# 5_4_transceiver.net
KiCad netlist of a schematic drawn in Altium Designer
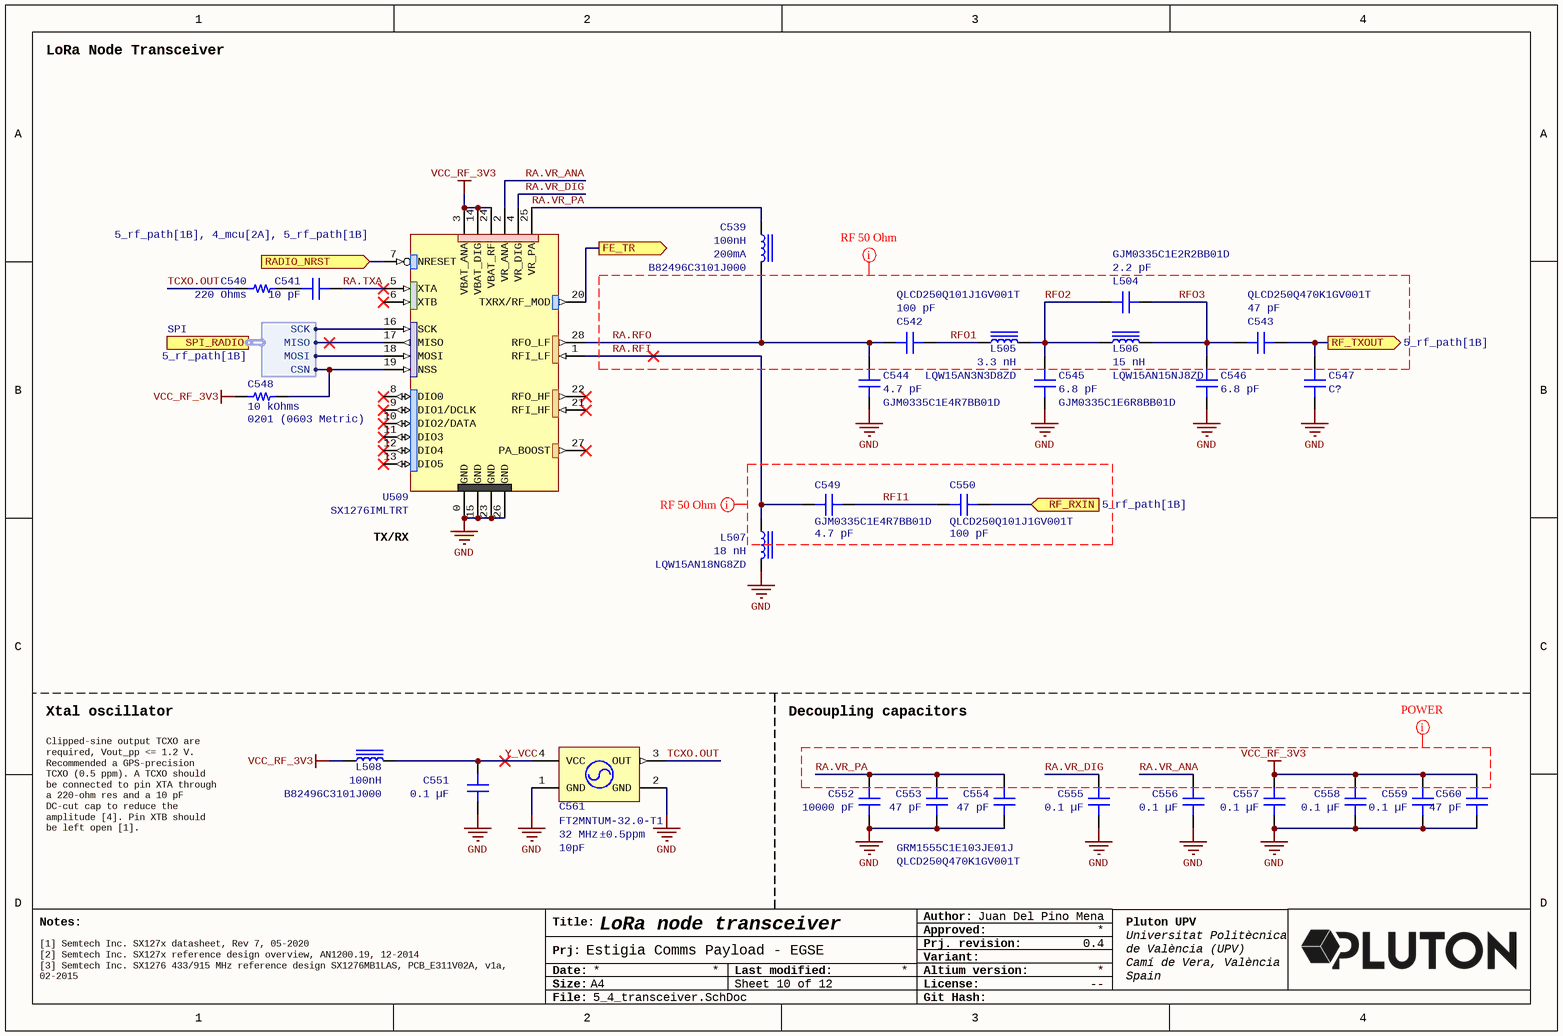
[diagram p0: 5_4_transceiver.SchDoc]

(export (version "E")
  (design (tool "Eeschema 10.0.6"))
  (components
    (comp (ref "C539")
      (value "100nH")
      (footprint "IND 0603_1608 RF WW")
      (description "FIXED IND 100NH 200MA 1.8 OHM")
      (fields
        (field (name "PART NUMBER") "B82496C3101J000")
        (field (name "CURRENT RATING (AMPS)") "200mA")
        (field (name "MANUFACTURER") "TDK Electronics Inc.")
        (field (name "TOLERANCE") "±5%")
      )
      (libsource (lib "Celestial Altium Library - altium_library") (part "Inductor"))
    )
    (comp (ref "C540")
      (value "220 Ohms")
      (footprint "RES 0201_0603")
      (description "RES 220 OHM 1% 1/20W 0201")
      (fields (field (name "PART NUMBER") "RC0201FR-07220RL") (field (name "MANUFACTURER") "Yageo"))
      (libsource (lib "Celestial Altium Library - altium_library") (part "Resistor"))
    )
    (comp (ref "C541")
      (value "10 pF")
      (footprint "CAP 0201_0603")
      (description "CAP CER 10PF 25V C0G/NP0 0201")
      (fields
        (field (name "PART NUMBER") "GJM0335C1E100GB01D")
        (field (name "MANUFACTURER") "Murata Electronics")
      )
      (libsource (lib "Celestial Altium Library - altium_library") (part "Capacitor"))
    )
    (comp (ref "C542")
      (value "100 pF")
      (footprint "CAP 0201_0603 RF")
      (description "CAP CER 100PF 25V C0G/NP0 0201")
      (fields
        (field (name "PART NUMBER") "QLCD250Q101J1GV001T")
        (field (name "CAPACITANCE") "100 pF")
        (field (name "MANUFACTURER") "Johanson Technology Inc.")
        (field (name "TOLERANCE") "±5%")
      )
      (libsource (lib "Celestial Altium Library - altium_library") (part "Capacitor"))
    )
    (comp (ref "C543")
      (value "47 pF")
      (footprint "CAP 0201_0603 RF")
      (description "CAP CER 47PF 25V NP0 0201")
      (fields
        (field (name "PART NUMBER") "QLCD250Q470K1GV001T")
        (field (name "CAPACITANCE") "47 pF")
        (field (name "MANUFACTURER") "Johanson Technology Inc.")
        (field (name "TOLERANCE") "±10%")
      )
      (libsource (lib "Celestial Altium Library - altium_library") (part "Capacitor"))
    )
    (comp (ref "C544")
      (value "4.7 pF")
      (footprint "CAP 0201_0603 RF")
      (description "CAP CER 4.7PF 25V C0G/NP0 0201")
      (fields
        (field (name "PART NUMBER") "GJM0335C1E4R7BB01D")
        (field (name "MANUFACTURER") "Murata Electronics")
        (field (name "TOLERANCE") "±0.1pF")
      )
      (libsource (lib "Celestial Altium Library - altium_library") (part "Capacitor"))
    )
    (comp (ref "C545")
      (value "6.8 pF")
      (footprint "CAP 0201_0603 RF")
      (description "CAP CER 6.8PF 25V C0G/NP0 0201")
      (fields
        (field (name "PART NUMBER") "GJM0335C1E6R8BB01D")
        (field (name "MANUFACTURER") "Murata Electronics")
        (field (name "TOLERANCE") "±0.1pF")
      )
      (libsource (lib "Celestial Altium Library - altium_library") (part "Capacitor"))
    )
    (comp (ref "C546")
      (value "6.8 pF")
      (footprint "CAP 0201_0603 RF")
      (description "CAP CER 6.8PF 25V C0G/NP0 0201")
      (fields
        (field (name "PART NUMBER") "GJM0335C1E6R8BB01D")
        (field (name "MANUFACTURER") "Murata Electronics")
      )
      (libsource (lib "Celestial Altium Library - altium_library") (part "Capacitor"))
    )
    (comp (ref "C547")
      (value "C?")
      (footprint "CAP 0201_0603")
      (description "CAP CER 2.2PF 25V C0G/NP0 0201")
      (fields
        (field (name "PART NUMBER") "GJM0335C1E2R2BB01D")
        (field (name "MANUFACTURER") "Murata Electronics")
      )
      (libsource (lib "Celestial Altium Library - altium_library") (part "Capacitor"))
    )
    (comp (ref "C548")
      (value "10 kOhms")
      (footprint "RES 0201_0603")
      (description "RES SMD 10K OHM 1% 1/20W 0201")
      (fields
        (field (name "PART NUMBER") "AF0201FR-0710KL")
        (field (name "MANUFACTURER") "Yageo")
        (field (name "PACKAGE / CASE") "0201 (0603 Metric)")
      )
      (libsource (lib "Celestial Altium Library - altium_library") (part "Resistor"))
    )
    (comp (ref "C549")
      (value "4.7 pF")
      (footprint "CAP 0201_0603 RF")
      (description "CAP CER 4.7PF 25V C0G/NP0 0201")
      (fields
        (field (name "PART NUMBER") "GJM0335C1E4R7BB01D")
        (field (name "MANUFACTURER") "Murata Electronics")
        (field (name "TOLERANCE") "±0.1pF")
      )
      (libsource (lib "Celestial Altium Library - altium_library") (part "Capacitor"))
    )
    (comp (ref "C550")
      (value "100 pF")
      (footprint "CAP 0201_0603 RF")
      (description "CAP CER 100PF 25V C0G/NP0 0201")
      (fields
        (field (name "PART NUMBER") "QLCD250Q101J1GV001T")
        (field (name "CAPACITANCE") "100 pF")
        (field (name "MANUFACTURER") "Johanson Technology Inc.")
        (field (name "TOLERANCE") "±5%")
      )
      (libsource (lib "Celestial Altium Library - altium_library") (part "Capacitor"))
    )
    (comp (ref "C551")
      (value "0.1 µF")
      (footprint "CAP 0402_1005")
      (description "CAP CER 0402 0.1UF 16V X7R 10%")
      (fields (field (name "PART NUMBER") "C0402C104K4RECAUTO") (field (name "MANUFACTURER") "KEMET"))
      (libsource (lib "Celestial Altium Library - altium_library") (part "Capacitor"))
    )
    (comp (ref "C552")
      (value "10000 pF")
      (footprint "CAP 0402_1005")
      (description "CAP CER 10000PF 25V C0G/NP0 0402")
      (fields
        (field (name "PART NUMBER") "GRM1555C1E103JE01J")
        (field (name "MANUFACTURER") "Murata Electronics")
        (field (name "TOLERANCE") "±5%")
      )
      (libsource (lib "Celestial Altium Library - altium_library") (part "Capacitor"))
    )
    (comp (ref "C553")
      (value "47 pF")
      (footprint "CAP 0201_0603 RF")
      (description "CAP CER 47PF 25V NP0 0201")
      (fields
        (field (name "PART NUMBER") "QLCD250Q470K1GV001T")
        (field (name "CAPACITANCE") "47 pF")
        (field (name "MANUFACTURER") "Johanson Technology Inc.")
      )
      (libsource (lib "Celestial Altium Library - altium_library") (part "Capacitor"))
    )
    (comp (ref "C554")
      (value "47 pF")
      (footprint "CAP 0201_0603 RF")
      (description "CAP CER 47PF 25V NP0 0201")
      (fields
        (field (name "PART NUMBER") "QLCD250Q470K1GV001T")
        (field (name "CAPACITANCE") "47 pF")
        (field (name "MANUFACTURER") "Johanson Technology Inc.")
        (field (name "TOLERANCE") "±10%")
      )
      (libsource (lib "Celestial Altium Library - altium_library") (part "Capacitor"))
    )
    (comp (ref "C555")
      (value "0.1 µF")
      (footprint "CAP 0402_1005")
      (description "CAP CER 0402 0.1UF 16V X7R 10%")
      (fields (field (name "PART NUMBER") "C0402C104K4RECAUTO") (field (name "MANUFACTURER") "KEMET"))
      (libsource (lib "Celestial Altium Library - altium_library") (part "Capacitor"))
    )
    (comp (ref "C556")
      (value "0.1 µF")
      (footprint "CAP 0402_1005")
      (description "CAP CER 0402 0.1UF 16V X7R 10%")
      (fields (field (name "PART NUMBER") "C0402C104K4RECAUTO") (field (name "MANUFACTURER") "KEMET"))
      (libsource (lib "Celestial Altium Library - altium_library") (part "Capacitor"))
    )
    (comp (ref "C557")
      (value "0.1 µF")
      (footprint "CAP 0402_1005")
      (description "CAP CER 0402 0.1UF 16V X7R 10%")
      (fields (field (name "PART NUMBER") "C0402C104K4RECAUTO") (field (name "MANUFACTURER") "KEMET"))
      (libsource (lib "Celestial Altium Library - altium_library") (part "Capacitor"))
    )
    (comp (ref "C558")
      (value "0.1 µF")
      (footprint "CAP 0402_1005")
      (description "CAP CER 0402 0.1UF 16V X7R 10%")
      (fields (field (name "PART NUMBER") "C0402C104K4RECAUTO") (field (name "MANUFACTURER") "KEMET"))
      (libsource (lib "Celestial Altium Library - altium_library") (part "Capacitor"))
    )
    (comp (ref "C559")
      (value "0.1 µF")
      (footprint "CAP 0402_1005")
      (description "CAP CER 0402 0.1UF 16V X7R 10%")
      (fields (field (name "PART NUMBER") "C0402C104K4RECAUTO") (field (name "MANUFACTURER") "KEMET"))
      (libsource (lib "Celestial Altium Library - altium_library") (part "Capacitor"))
    )
    (comp (ref "C560")
      (value "47 pF")
      (footprint "CAP 0201_0603 RF")
      (description "CAP CER 47PF 25V NP0 0201")
      (fields
        (field (name "PART NUMBER") "QLCD250Q470K1GV001T")
        (field (name "CAPACITANCE") "47 pF")
        (field (name "MANUFACTURER") "Johanson Technology Inc.")
      )
      (libsource (lib "Celestial Altium Library - altium_library") (part "Capacitor"))
    )
    (comp (ref "C561")
      (value "FT2MNTUM-32.0-T1")
      (footprint "TCXO-XTAL-FT2MN")
      (fields
        (field (name "PART NUMBER") "FT2MNTUM-32.0-T1")
        (field (name "FREQUENCY") "32 MHz")
        (field (name "TOLERANCE") "±0.5ppm")
        (field (name "LOAD CAPACITANCE") "10pF")
      )
      (libsource (lib "rf") (part "FT2MNTUM-32.0-T1"))
    )
    (comp (ref "L504")
      (value "2.2 pF")
      (footprint "CAP 0201_0603")
      (description "CAP CER 2.2PF 25V C0G/NP0 0201")
      (fields
        (field (name "PART NUMBER") "GJM0335C1E2R2BB01D")
        (field (name "MANUFACTURER") "Murata Electronics")
        (field (name "TOLERANCE") "±0.1pF")
      )
      (libsource (lib "Celestial Altium Library - altium_library") (part "Capacitor"))
    )
    (comp (ref "L505")
      (value "3.3 nH")
      (footprint "IND 0402_1005 RF WW")
      (description "FIXED IND 3.3NH 2A 0.03OHM SMD")
      (fields
        (field (name "PART NUMBER") "LQW15AN3N3D8ZD")
        (field (name "INDUCTANCE") "3.3 nH")
        (field (name "MANUFACTURER") "Murata Electronics")
        (field (name "TOLERANCE") "±0.5nH")
      )
      (libsource (lib "Celestial Altium Library - altium_library") (part "Inductor"))
    )
    (comp (ref "L506")
      (value "15 nH")
      (footprint "IND 0402_1005 RF WW")
      (description "FIXED IND 15NH 1.15A 0.114OHM SM")
      (fields
        (field (name "PART NUMBER") "LQW15AN15NJ8ZD")
        (field (name "INDUCTANCE") "15 nH")
        (field (name "MANUFACTURER") "Murata Electronics")
        (field (name "TOLERANCE") "±5%")
      )
      (libsource (lib "Celestial Altium Library - altium_library") (part "Inductor"))
    )
    (comp (ref "L507")
      (value "18 nH")
      (footprint "IND 0402_1005 RF WW")
      (description "FIXED IND 18NH 1.05A 0.13OHM SMD")
      (fields
        (field (name "PART NUMBER") "LQW15AN18NG8ZD")
        (field (name "INDUCTANCE") "18 nH")
        (field (name "MANUFACTURER") "Murata Electronics")
        (field (name "TOLERANCE") "±2%")
      )
      (libsource (lib "Celestial Altium Library - altium_library") (part "Inductor"))
    )
    (comp (ref "L508")
      (value "100nH")
      (footprint "IND 0603_1608 RF WW")
      (description "FIXED IND 100NH 200MA 1.8 OHM")
      (fields
        (field (name "PART NUMBER") "B82496C3101J000")
        (field (name "MANUFACTURER") "TDK Electronics Inc.")
        (field (name "TOLERANCE") "±5%")
      )
      (libsource (lib "Celestial Altium Library - altium_library") (part "Inductor"))
    )
    (comp (ref "U509")
      (value "SX1276IMLTRT")
      (footprint "ics:QFN-28")
      (description "137 MHz to 1020 MHz Low Power Long Range Transceiver")
      (libsource (lib "lora") (part "SX1276IMLTRT"))
    )
  )
  (nets
    (net (code "2") (name "/CSN") (class "Default")
      (node (ref "C548") (pin "2") (pinfunction "2_2") (pintype "passive"))
      (node (ref "U509") (pin "19") (pinfunction "NSS_19") (pintype "input"))
    )
    (net (code "3") (name "/FE_TR") (class "Default")
      (node (ref "U509") (pin "20") (pinfunction "TXRX/RF_MOD_20") (pintype "output"))
    )
    (net (code "4") (name "/MISO") (class "Default")
      (node (ref "U509") (pin "17") (pinfunction "MISO_17") (pintype "output"))
    )
    (net (code "5") (name "/MOSI") (class "Default")
      (node (ref "U509") (pin "18") (pinfunction "MOSI_18") (pintype "input"))
    )
    (net (code "7") (name "/RA.RFI") (class "Default")
      (node (ref "C549") (pin "2") (pinfunction "2_2") (pintype "passive"))
      (node (ref "L507") (pin "1") (pinfunction "1_1") (pintype "passive"))
      (node (ref "U509") (pin "1") (pinfunction "RFI_LF_1") (pintype "input"))
    )
    (net (code "8") (name "/RA.RFO") (class "Default")
      (node (ref "C539") (pin "2") (pinfunction "2_2") (pintype "passive"))
      (node (ref "C542") (pin "1") (pinfunction "1_1") (pintype "passive"))
      (node (ref "C544") (pin "2") (pinfunction "2_2") (pintype "passive"))
      (node (ref "U509") (pin "28") (pinfunction "RFO_LF_28") (pintype "output"))
    )
    (net (code "9") (name "/RA.TXA") (class "Default")
      (node (ref "C541") (pin "1") (pinfunction "1_1") (pintype "passive"))
      (node (ref "U509") (pin "5") (pinfunction "XTA_5") (pintype "input"))
    )
    (net (code "10") (name "/RA.VR_ANA") (class "Default")
      (node (ref "C556") (pin "2") (pinfunction "2_2") (pintype "passive"))
      (node (ref "U509") (pin "2") (pinfunction "VR_ANA_2") (pintype "power_in"))
    )
    (net (code "11") (name "/RA.VR_DIG") (class "Default")
      (node (ref "C555") (pin "2") (pinfunction "2_2") (pintype "passive"))
      (node (ref "U509") (pin "4") (pinfunction "VR_DIG_4") (pintype "power_in"))
    )
    (net (code "12") (name "/RA.VR_PA") (class "Default")
      (node (ref "C539") (pin "1") (pinfunction "1_1") (pintype "passive"))
      (node (ref "C552") (pin "2") (pinfunction "2_2") (pintype "passive"))
      (node (ref "C553") (pin "2") (pinfunction "2_2") (pintype "passive"))
      (node (ref "C554") (pin "1") (pinfunction "1_1") (pintype "passive"))
      (node (ref "U509") (pin "25") (pinfunction "VR_PA_25") (pintype "power_in"))
    )
    (net (code "13") (name "/RADIO_NRST") (class "Default")
      (node (ref "U509") (pin "7") (pinfunction "NRESET_7") (pintype "input"))
    )
    (net (code "14") (name "/RFI1") (class "Default")
      (node (ref "C549") (pin "1") (pinfunction "1_1") (pintype "passive"))
      (node (ref "C550") (pin "2") (pinfunction "2_2") (pintype "passive"))
    )
    (net (code "15") (name "/RFO1") (class "Default")
      (node (ref "C542") (pin "2") (pinfunction "2_2") (pintype "passive"))
      (node (ref "L505") (pin "1") (pinfunction "1_1") (pintype "passive"))
    )
    (net (code "16") (name "/RFO2") (class "Default")
      (node (ref "C545") (pin "2") (pinfunction "2_2") (pintype "passive"))
      (node (ref "L504") (pin "1") (pinfunction "1_1") (pintype "passive"))
      (node (ref "L505") (pin "2") (pinfunction "2_2") (pintype "passive"))
      (node (ref "L506") (pin "1") (pinfunction "1_1") (pintype "passive"))
    )
    (net (code "17") (name "/RFO3") (class "Default")
      (node (ref "C543") (pin "1") (pinfunction "1_1") (pintype "passive"))
      (node (ref "C546") (pin "2") (pinfunction "2_2") (pintype "passive"))
      (node (ref "L504") (pin "2") (pinfunction "2_2") (pintype "passive"))
      (node (ref "L506") (pin "2") (pinfunction "2_2") (pintype "passive"))
    )
    (net (code "18") (name "/RF_RXIN") (class "Default")
      (node (ref "C550") (pin "1") (pinfunction "1_1") (pintype "passive"))
    )
    (net (code "19") (name "/RF_TXOUT") (class "Default")
      (node (ref "C543") (pin "2") (pinfunction "2_2") (pintype "passive"))
      (node (ref "C547") (pin "2") (pinfunction "2_2") (pintype "passive"))
    )
    (net (code "20") (name "/SCK") (class "Default")
      (node (ref "U509") (pin "16") (pinfunction "SCK_16") (pintype "input"))
    )
    (net (code "23") (name "/TCXO.OUT") (class "Default")
      (node (ref "C540") (pin "1") (pinfunction "1_1") (pintype "passive"))
      (node (ref "C561") (pin "3") (pinfunction "OUT_3") (pintype "output"))
    )
    (net (code "24") (name "/Y_VCC") (class "Default")
      (node (ref "C551") (pin "2") (pinfunction "2_2") (pintype "passive"))
      (node (ref "C561") (pin "4") (pinfunction "VCC_4") (pintype "power_in"))
      (node (ref "L508") (pin "2") (pinfunction "2_2") (pintype "passive"))
    )
    (net (code "25") (name "GND") (class "Default")
      (node (ref "C544") (pin "1") (pinfunction "1_1") (pintype "passive"))
      (node (ref "C545") (pin "1") (pinfunction "1_1") (pintype "passive"))
      (node (ref "C546") (pin "1") (pinfunction "1_1") (pintype "passive"))
      (node (ref "C547") (pin "1") (pinfunction "1_1") (pintype "passive"))
      (node (ref "C551") (pin "1") (pinfunction "1_1") (pintype "passive"))
      (node (ref "C552") (pin "1") (pinfunction "1_1") (pintype "passive"))
      (node (ref "C553") (pin "1") (pinfunction "1_1") (pintype "passive"))
      (node (ref "C554") (pin "2") (pinfunction "2_2") (pintype "passive"))
      (node (ref "C555") (pin "1") (pinfunction "1_1") (pintype "passive"))
      (node (ref "C556") (pin "1") (pinfunction "1_1") (pintype "passive"))
      (node (ref "C557") (pin "1") (pinfunction "1_1") (pintype "passive"))
      (node (ref "C558") (pin "1") (pinfunction "1_1") (pintype "passive"))
      (node (ref "C559") (pin "1") (pinfunction "1_1") (pintype "passive"))
      (node (ref "C560") (pin "1") (pinfunction "1_1") (pintype "passive"))
      (node (ref "C561") (pin "1") (pinfunction "GND_1") (pintype "power_in"))
      (node (ref "C561") (pin "2") (pinfunction "GND_2") (pintype "power_in"))
      (node (ref "L507") (pin "2") (pinfunction "2_2") (pintype "passive"))
      (node (ref "U509") (pin "0") (pinfunction "GND_0") (pintype "power_in"))
      (node (ref "U509") (pin "15") (pinfunction "GND_15") (pintype "power_in"))
      (node (ref "U509") (pin "23") (pinfunction "GND_23") (pintype "power_in"))
      (node (ref "U509") (pin "26") (pinfunction "GND_26") (pintype "power_in"))
    )
    (net (code "26") (name "Net-(C540-Pad2)") (class "Default")
      (node (ref "C540") (pin "2") (pinfunction "2_2") (pintype "passive"))
      (node (ref "C541") (pin "2") (pinfunction "2_2") (pintype "passive"))
    )
    (net (code "27") (name "VCC_RF_3V3") (class "Default")
      (node (ref "C548") (pin "1") (pinfunction "1_1") (pintype "passive"))
      (node (ref "C557") (pin "2") (pinfunction "2_2") (pintype "passive"))
      (node (ref "C558") (pin "2") (pinfunction "2_2") (pintype "passive"))
      (node (ref "C559") (pin "2") (pinfunction "2_2") (pintype "passive"))
      (node (ref "C560") (pin "2") (pinfunction "2_2") (pintype "passive"))
      (node (ref "L508") (pin "1") (pinfunction "1_1") (pintype "passive"))
      (node (ref "U509") (pin "14") (pinfunction "VBAT_DIG_14") (pintype "power_in"))
      (node (ref "U509") (pin "24") (pinfunction "VBAT_RF_24") (pintype "power_in"))
      (node (ref "U509") (pin "3") (pinfunction "VBAT_ANA_3") (pintype "power_in"))
    )
    (net (code "28") (name "unconnected-(U509-DIO0-Pad8)") (class "Default")
      (node (ref "U509") (pin "8") (pinfunction "DIO0_8") (pintype "bidirectional+no_connect"))
    )
    (net (code "29") (name "unconnected-(U509-DIO1{slash}DCLK-Pad9)") (class "Default")
      (node (ref "U509") (pin "9") (pinfunction "DIO1/DCLK_9") (pintype "bidirectional+no_connect"))
    )
    (net (code "30") (name "unconnected-(U509-DIO2{slash}DATA-Pad10)") (class "Default")
      (node (ref "U509") (pin "10") (pinfunction "DIO2/DATA_10") (pintype "bidirectional+no_connect"))
    )
    (net (code "31") (name "unconnected-(U509-DIO3-Pad11)") (class "Default")
      (node (ref "U509") (pin "11") (pinfunction "DIO3_11") (pintype "bidirectional+no_connect"))
    )
    (net (code "32") (name "unconnected-(U509-DIO4-Pad12)") (class "Default")
      (node (ref "U509") (pin "12") (pinfunction "DIO4_12") (pintype "bidirectional+no_connect"))
    )
    (net (code "33") (name "unconnected-(U509-DIO5-Pad13)") (class "Default")
      (node (ref "U509") (pin "13") (pinfunction "DIO5_13") (pintype "bidirectional+no_connect"))
    )
    (net (code "34") (name "unconnected-(U509-PA_BOOST-Pad27)") (class "Default")
      (node (ref "U509") (pin "27") (pinfunction "PA_BOOST_27") (pintype "output+no_connect"))
    )
    (net (code "35") (name "unconnected-(U509-RFI_HF-Pad21)") (class "Default")
      (node (ref "U509") (pin "21") (pinfunction "RFI_HF_21") (pintype "input+no_connect"))
    )
    (net (code "36") (name "unconnected-(U509-RFO_HF-Pad22)") (class "Default")
      (node (ref "U509") (pin "22") (pinfunction "RFO_HF_22") (pintype "output+no_connect"))
    )
    (net (code "37") (name "unconnected-(U509-XTB-Pad6)") (class "Default")
      (node (ref "U509") (pin "6") (pinfunction "XTB_6") (pintype "input+no_connect"))
    )
  )
)
